# DHT11_Board.net
KiCad netlist of a schematic drawn in EAGLE
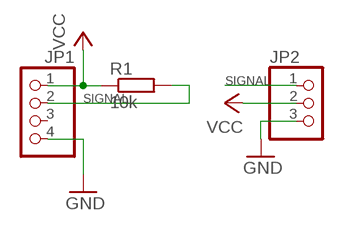
[diagram p0: schematic, sheet 1]

(export (version "E")
  (design (tool "Eeschema 10.0.6"))
  (components
    (comp (ref "JP1")
      (value "PINHD-1X4")
      (footprint "eagle-import:1X04")
      (libsource (lib "eagle-import") (part "PINHD-1X4"))
    )
    (comp (ref "JP2")
      (value "PINHD-1X3")
      (footprint "eagle-import:1X03")
      (libsource (lib "eagle-import") (part "PINHD-1X3"))
    )
    (comp (ref "R1")
      (value "10k")
      (footprint "eagle-import:0204_7")
      (libsource (lib "eagle-import") (part "R-EU_0204/7"))
    )
  )
  (nets
    (net (code "1") (name "/SIGNAL") (class "Default")
      (node (ref "JP1") (pin "2") (pinfunction "2_2") (pintype "passive"))
      (node (ref "JP2") (pin "1") (pinfunction "1_1") (pintype "passive"))
      (node (ref "R1") (pin "2") (pinfunction "2_2") (pintype "passive"))
    )
    (net (code "2") (name "GND") (class "Default")
      (node (ref "JP1") (pin "4") (pinfunction "4_4") (pintype "passive"))
      (node (ref "JP2") (pin "3") (pinfunction "3_3") (pintype "passive"))
    )
    (net (code "3") (name "VCC") (class "Default")
      (node (ref "JP1") (pin "1") (pinfunction "1_1") (pintype "passive"))
      (node (ref "JP2") (pin "2") (pinfunction "2_2") (pintype "passive"))
      (node (ref "R1") (pin "1") (pinfunction "1_1") (pintype "passive"))
    )
    (net (code "4") (name "unconnected-(JP1-Pad3)") (class "Default")
      (node (ref "JP1") (pin "3") (pinfunction "3_3") (pintype "passive"))
    )
  )
)
